# Lowduino_Minimal_ZIF.net
KiCad netlist of a schematic drawn in EAGLE
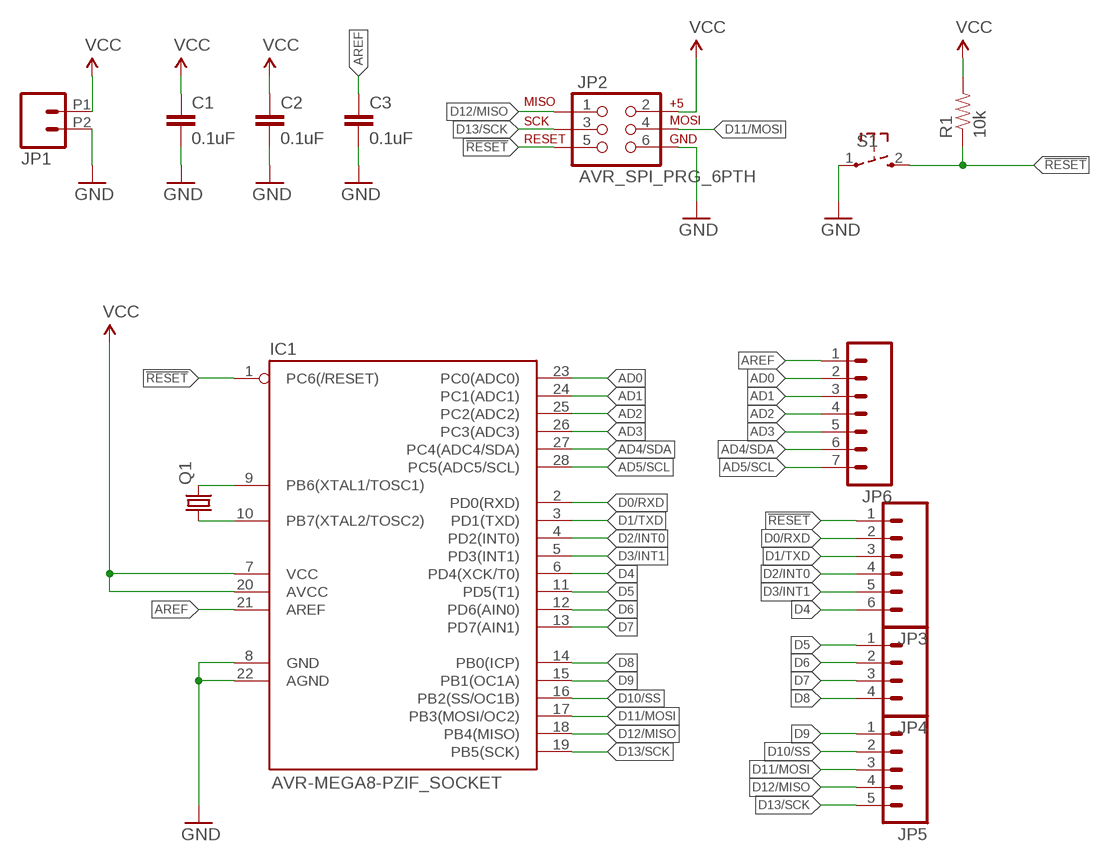
[diagram p0: schematic, sheet 1]

(export (version "E")
  (design (tool "Eeschema 10.0.6"))
  (components
    (comp (ref "C1")
      (value "0.1uF")
      (footprint "eagle-import:CAP-PTH-SMALL")
      (libsource (lib "eagle-import") (part "CAPPTH"))
    )
    (comp (ref "C2")
      (value "0.1uF")
      (footprint "eagle-import:CAP-PTH-SMALL")
      (libsource (lib "eagle-import") (part "CAPPTH"))
    )
    (comp (ref "C3")
      (value "0.1uF")
      (footprint "eagle-import:CAP-PTH-SMALL")
      (libsource (lib "eagle-import") (part "CAPPTH"))
    )
    (comp (ref "IC1")
      (value "AVR-MEGA8-PZIF_SOCKET")
      (footprint "eagle-import:DIL28-3-ZIF_SOCKET")
      (libsource (lib "eagle-import") (part "AVR-MEGA8-PZIF_SOCKET"))
    )
    (comp (ref "JP1")
      (value "M022.54MM_SCREWTERM")
      (footprint "eagle-import:1X02_2.54_SCREWTERM")
      (libsource (lib "eagle-import") (part "M022.54MM_SCREWTERM"))
    )
    (comp (ref "JP2")
      (value "AVR_SPI_PRG_6PTH")
      (footprint "eagle-import:2X3")
      (libsource (lib "eagle-import") (part "AVR_SPI_PRG_6PTH"))
    )
    (comp (ref "JP3")
      (value "M06LOCK")
      (footprint "eagle-import:1X06_LOCK")
      (libsource (lib "eagle-import") (part "M06LOCK"))
    )
    (comp (ref "JP4")
      (value "M04LOCK")
      (footprint "eagle-import:1X04_LOCK")
      (libsource (lib "eagle-import") (part "M04LOCK"))
    )
    (comp (ref "JP5")
      (value "M05LOCK")
      (footprint "eagle-import:1X05_LOCK")
      (libsource (lib "eagle-import") (part "M05LOCK"))
    )
    (comp (ref "JP6")
      (value "M07LOCK")
      (footprint "eagle-import:1X07_LOCK")
      (libsource (lib "eagle-import") (part "M07LOCK"))
    )
    (comp (ref "Q1")
      (value "CRYSTALTC26V")
      (footprint "eagle-import:TC26V")
      (libsource (lib "eagle-import") (part "CRYSTALTC26V"))
    )
    (comp (ref "R1")
      (value "10k")
      (footprint "eagle-import:AXIAL-0.1")
      (libsource (lib "eagle-import") (part "10KOHM-1/4W5%(PTH)VERT"))
    )
    (comp (ref "S1")
      (value "MJTP_6MM")
      (footprint "eagle-import:MJTP1243")
      (libsource (lib "eagle-import") (part "MJTP_6MM"))
    )
  )
  (nets
    (net (code "1") (name "/~{RESET}") (class "Default")
      (node (ref "IC1") (pin "1") (pinfunction "PC6(/RESET)_1") (pintype "bidirectional"))
      (node (ref "JP2") (pin "5") (pinfunction "5_5") (pintype "passive"))
      (node (ref "JP3") (pin "1") (pinfunction "1_1") (pintype "passive"))
      (node (ref "R1") (pin "P$1") (pinfunction "1_P$1") (pintype "passive"))
      (node (ref "S1") (pin "2") (pinfunction "3_2") (pintype "passive"))
    )
    (net (code "2") (name "AD0") (class "Default")
      (node (ref "IC1") (pin "23") (pinfunction "PC0(ADC0)_23") (pintype "bidirectional"))
      (node (ref "JP6") (pin "2") (pinfunction "2_2") (pintype "passive"))
    )
    (net (code "3") (name "AD1") (class "Default")
      (node (ref "IC1") (pin "24") (pinfunction "PC1(ADC1)_24") (pintype "bidirectional"))
      (node (ref "JP6") (pin "3") (pinfunction "3_3") (pintype "passive"))
    )
    (net (code "4") (name "AD2") (class "Default")
      (node (ref "IC1") (pin "25") (pinfunction "PC2(ADC2)_25") (pintype "bidirectional"))
      (node (ref "JP6") (pin "4") (pinfunction "4_4") (pintype "passive"))
    )
    (net (code "5") (name "AD3") (class "Default")
      (node (ref "IC1") (pin "26") (pinfunction "PC3(ADC3)_26") (pintype "bidirectional"))
      (node (ref "JP6") (pin "5") (pinfunction "5_5") (pintype "passive"))
    )
    (net (code "6") (name "AD4{slash}SDA") (class "Default")
      (node (ref "IC1") (pin "27") (pinfunction "PC4(ADC4/SDA)_27") (pintype "bidirectional"))
      (node (ref "JP6") (pin "6") (pinfunction "6_6") (pintype "passive"))
    )
    (net (code "7") (name "AD5{slash}SCL") (class "Default")
      (node (ref "IC1") (pin "28") (pinfunction "PC5(ADC5/SCL)_28") (pintype "bidirectional"))
      (node (ref "JP6") (pin "7") (pinfunction "7_7") (pintype "passive"))
    )
    (net (code "8") (name "AREF") (class "Default")
      (node (ref "C3") (pin "1") (pinfunction "1_1") (pintype "passive"))
      (node (ref "IC1") (pin "21") (pinfunction "AREF_21") (pintype "bidirectional"))
      (node (ref "JP6") (pin "1") (pinfunction "1_1") (pintype "passive"))
    )
    (net (code "9") (name "D0{slash}RXD") (class "Default")
      (node (ref "IC1") (pin "2") (pinfunction "PD0(RXD)_2") (pintype "bidirectional"))
      (node (ref "JP3") (pin "2") (pinfunction "2_2") (pintype "passive"))
    )
    (net (code "10") (name "D1{slash}TXD") (class "Default")
      (node (ref "IC1") (pin "3") (pinfunction "PD1(TXD)_3") (pintype "bidirectional"))
      (node (ref "JP3") (pin "3") (pinfunction "3_3") (pintype "passive"))
    )
    (net (code "11") (name "D2{slash}INT0") (class "Default")
      (node (ref "IC1") (pin "4") (pinfunction "PD2(INT0)_4") (pintype "bidirectional"))
      (node (ref "JP3") (pin "4") (pinfunction "4_4") (pintype "passive"))
    )
    (net (code "12") (name "D3{slash}INT1") (class "Default")
      (node (ref "IC1") (pin "5") (pinfunction "PD3(INT1)_5") (pintype "bidirectional"))
      (node (ref "JP3") (pin "5") (pinfunction "5_5") (pintype "passive"))
    )
    (net (code "13") (name "D4") (class "Default")
      (node (ref "IC1") (pin "6") (pinfunction "PD4(XCK/T0)_6") (pintype "bidirectional"))
      (node (ref "JP3") (pin "6") (pinfunction "6_6") (pintype "passive"))
    )
    (net (code "14") (name "D5") (class "Default")
      (node (ref "IC1") (pin "11") (pinfunction "PD5(T1)_11") (pintype "bidirectional"))
      (node (ref "JP4") (pin "1") (pinfunction "1_1") (pintype "passive"))
    )
    (net (code "15") (name "D6") (class "Default")
      (node (ref "IC1") (pin "12") (pinfunction "PD6(AIN0)_12") (pintype "bidirectional"))
      (node (ref "JP4") (pin "2") (pinfunction "2_2") (pintype "passive"))
    )
    (net (code "16") (name "D7") (class "Default")
      (node (ref "IC1") (pin "13") (pinfunction "PD7(AIN1)_13") (pintype "bidirectional"))
      (node (ref "JP4") (pin "3") (pinfunction "3_3") (pintype "passive"))
    )
    (net (code "17") (name "D8") (class "Default")
      (node (ref "IC1") (pin "14") (pinfunction "PB0(ICP)_14") (pintype "bidirectional"))
      (node (ref "JP4") (pin "4") (pinfunction "4_4") (pintype "passive"))
    )
    (net (code "18") (name "D9") (class "Default")
      (node (ref "IC1") (pin "15") (pinfunction "PB1(OC1A)_15") (pintype "bidirectional"))
      (node (ref "JP5") (pin "1") (pinfunction "1_1") (pintype "passive"))
    )
    (net (code "19") (name "D10{slash}SS") (class "Default")
      (node (ref "IC1") (pin "16") (pinfunction "PB2(SS/OC1B)_16") (pintype "bidirectional"))
      (node (ref "JP5") (pin "2") (pinfunction "2_2") (pintype "passive"))
    )
    (net (code "20") (name "D11{slash}MOSI") (class "Default")
      (node (ref "IC1") (pin "17") (pinfunction "PB3(MOSI/OC2)_17") (pintype "bidirectional"))
      (node (ref "JP2") (pin "4") (pinfunction "4_4") (pintype "passive"))
      (node (ref "JP5") (pin "3") (pinfunction "3_3") (pintype "passive"))
    )
    (net (code "21") (name "D12{slash}MISO") (class "Default")
      (node (ref "IC1") (pin "18") (pinfunction "PB4(MISO)_18") (pintype "bidirectional"))
      (node (ref "JP2") (pin "1") (pinfunction "1_1") (pintype "passive"))
      (node (ref "JP5") (pin "4") (pinfunction "4_4") (pintype "passive"))
    )
    (net (code "22") (name "D13{slash}SCK") (class "Default")
      (node (ref "IC1") (pin "19") (pinfunction "PB5(SCK)_19") (pintype "bidirectional"))
      (node (ref "JP2") (pin "3") (pinfunction "3_3") (pintype "passive"))
      (node (ref "JP5") (pin "5") (pinfunction "5_5") (pintype "passive"))
    )
    (net (code "23") (name "GND") (class "Default")
      (node (ref "C1") (pin "2") (pinfunction "2_2") (pintype "passive"))
      (node (ref "C2") (pin "2") (pinfunction "2_2") (pintype "passive"))
      (node (ref "C3") (pin "2") (pinfunction "2_2") (pintype "passive"))
      (node (ref "IC1") (pin "22") (pinfunction "AGND_22") (pintype "bidirectional"))
      (node (ref "IC1") (pin "8") (pinfunction "GND_8") (pintype "bidirectional"))
      (node (ref "JP1") (pin "P2") (pinfunction "2_P2") (pintype "passive"))
      (node (ref "JP2") (pin "6") (pinfunction "6_6") (pintype "passive"))
      (node (ref "S1") (pin "1") (pinfunction "1_1") (pintype "passive"))
    )
    (net (code "24") (name "Net-(IC1-PB6(XTAL1{slash}TOSC1))") (class "Default")
      (node (ref "IC1") (pin "9") (pinfunction "PB6(XTAL1/TOSC1)_9") (pintype "bidirectional"))
      (node (ref "Q1") (pin "2") (pinfunction "2_2") (pintype "passive"))
    )
    (net (code "25") (name "Net-(IC1-PB7(XTAL2{slash}TOSC2))") (class "Default")
      (node (ref "IC1") (pin "10") (pinfunction "PB7(XTAL2/TOSC2)_10") (pintype "bidirectional"))
      (node (ref "Q1") (pin "1") (pinfunction "1_1") (pintype "passive"))
    )
    (net (code "26") (name "VCC") (class "Default")
      (node (ref "C1") (pin "1") (pinfunction "1_1") (pintype "passive"))
      (node (ref "C2") (pin "1") (pinfunction "1_1") (pintype "passive"))
      (node (ref "IC1") (pin "20") (pinfunction "AVCC_20") (pintype "bidirectional"))
      (node (ref "IC1") (pin "7") (pinfunction "VCC_7") (pintype "bidirectional"))
      (node (ref "JP1") (pin "P1") (pinfunction "1_P1") (pintype "passive"))
      (node (ref "JP2") (pin "2") (pinfunction "2_2") (pintype "passive"))
      (node (ref "R1") (pin "P$2") (pinfunction "2_P$2") (pintype "passive"))
    )
  )
)
